# ADC.net
KiCad netlist of a schematic drawn in Altium Designer
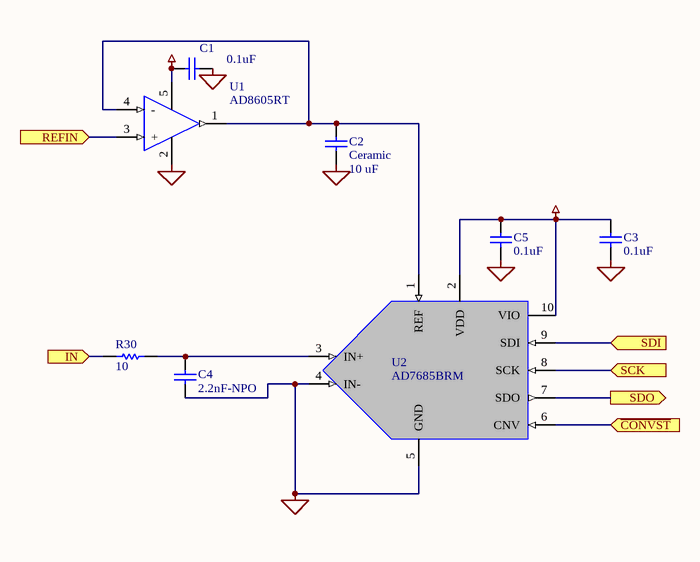
[diagram p0: ADC.SCHDOC]

(export (version "E")
  (design (tool "Eeschema 10.0.6"))
  (components
    (comp (ref "C1")
      (value "0.1uF")
      (footprint "CC1608-0603")
      (description "Capacitor")
      (fields
        (field (name "MANUFACTURER") "Generic Components")
        (field (name "Comment") "Cap")
        (field (name "PUBLISHER") "Altium Limited")
      )
      (libsource (lib "Miscellaneous Devices") (part "Cap"))
    )
    (comp (ref "C2")
      (value "Ceramic")
      (footprint "0805")
      (description "Capacitor")
      (fields (field (name "ALTIUM_VALUE") "10 uF") (field (name "PUBLISHER") "Altium Limited"))
      (libsource (lib "Miscellaneous Devices") (part "Cap"))
    )
    (comp (ref "C3")
      (value "0.1uF")
      (footprint "CC1608-0603")
      (description "Capacitor")
      (fields
        (field (name "MANUFACTURER") "Generic Components")
        (field (name "Comment") "Cap")
        (field (name "PUBLISHER") "Altium Limited")
      )
      (libsource (lib "Miscellaneous Devices") (part "Cap"))
    )
    (comp (ref "C4")
      (value "2.2nF-NPO")
      (footprint "0603")
      (description "Capacitor")
      (fields (field (name "Comment") "Cap") (field (name "PUBLISHER") "Altium Limited"))
      (libsource (lib "Miscellaneous Devices") (part "Cap"))
    )
    (comp (ref "C5")
      (value "0.1uF")
      (footprint "CC1608-0603")
      (description "Capacitor")
      (fields
        (field (name "MANUFACTURER") "Generic Components")
        (field (name "Comment") "Cap")
        (field (name "PUBLISHER") "Altium Limited")
      )
      (libsource (lib "Miscellaneous Devices") (part "Cap"))
    )
    (comp (ref "R30")
      (value "10")
      (footprint "0603")
      (description "Resistor")
      (fields (field (name "Comment") "Res1") (field (name "PUBLISHER") "Altium Limited"))
      (libsource (lib "Miscellaneous Devices") (part "Res1"))
    )
    (comp (ref "U1")
      (value "AD8605RT")
      (footprint "SO-G5/P.95")
      (description "Analog Devices Precision Low Noise CMOS Rail-to-Rail Input/Output Operational Amplifier")
      (libsource (lib "parts") (part "AD8605RT"))
    )
    (comp (ref "U2")
      (value "AD7685BRM")
      (footprint "AD RM-10")
      (description "AD 16-bit 250 kSPS ADC")
      (libsource (lib "parts") (part "AD7685"))
    )
  )
  (nets
    (net (code "1") (name "/IN") (class "Default")
      (node (ref "R30") (pin "1") (pinfunction "1_1") (pintype "passive"))
    )
    (net (code "2") (name "/REFIN") (class "Default")
      (node (ref "U1") (pin "3") (pinfunction "+_3") (pintype "input"))
    )
    (net (code "3") (name "/SCK") (class "Default")
      (node (ref "U2") (pin "8") (pinfunction "SCK_8") (pintype "input"))
    )
    (net (code "4") (name "/SDI") (class "Default")
      (node (ref "U2") (pin "9") (pinfunction "SDI_9") (pintype "input"))
    )
    (net (code "5") (name "/SDO") (class "Default")
      (node (ref "U2") (pin "7") (pinfunction "SDO_7") (pintype "output"))
    )
    (net (code "6") (name "/~{CONVST}") (class "Default")
      (node (ref "U2") (pin "6") (pinfunction "CNV_6") (pintype "input"))
    )
    (net (code "7") (name "AGND") (class "Default")
      (node (ref "C1") (pin "2") (pinfunction "2_2") (pintype "passive"))
      (node (ref "C2") (pin "1") (pinfunction "1_1") (pintype "passive"))
      (node (ref "C3") (pin "1") (pinfunction "1_1") (pintype "passive"))
      (node (ref "C4") (pin "1") (pinfunction "1_1") (pintype "passive"))
      (node (ref "C5") (pin "1") (pinfunction "1_1") (pintype "passive"))
      (node (ref "U1") (pin "2") (pinfunction "-Vs_2") (pintype "power_in"))
      (node (ref "U2") (pin "4") (pinfunction "IN-_4") (pintype "input"))
      (node (ref "U2") (pin "5") (pinfunction "GND_5") (pintype "power_in"))
    )
    (net (code "8") (name "AVDD") (class "Default")
      (node (ref "C1") (pin "1") (pinfunction "1_1") (pintype "passive"))
      (node (ref "C3") (pin "2") (pinfunction "2_2") (pintype "passive"))
      (node (ref "C5") (pin "2") (pinfunction "2_2") (pintype "passive"))
      (node (ref "U1") (pin "5") (pinfunction "+Vs_5") (pintype "power_in"))
      (node (ref "U2") (pin "10") (pinfunction "VIO_10") (pintype "power_in"))
      (node (ref "U2") (pin "2") (pinfunction "VDD_2") (pintype "power_in"))
    )
    (net (code "9") (name "Net-(U1--)") (class "Default")
      (node (ref "C2") (pin "2") (pinfunction "2_2") (pintype "passive"))
      (node (ref "U1") (pin "1") (pinfunction "Out_1") (pintype "output"))
      (node (ref "U1") (pin "4") (pinfunction "-_4") (pintype "input"))
      (node (ref "U2") (pin "1") (pinfunction "REF_1") (pintype "input"))
    )
    (net (code "10") (name "Net-(U2-IN+)") (class "Default")
      (node (ref "C4") (pin "2") (pinfunction "2_2") (pintype "passive"))
      (node (ref "R30") (pin "2") (pinfunction "2_2") (pintype "passive"))
      (node (ref "U2") (pin "3") (pinfunction "IN+_3") (pintype "input"))
    )
  )
)
